# umni-ultra-controller.net
KiCad netlist of a schematic drawn in EAGLE
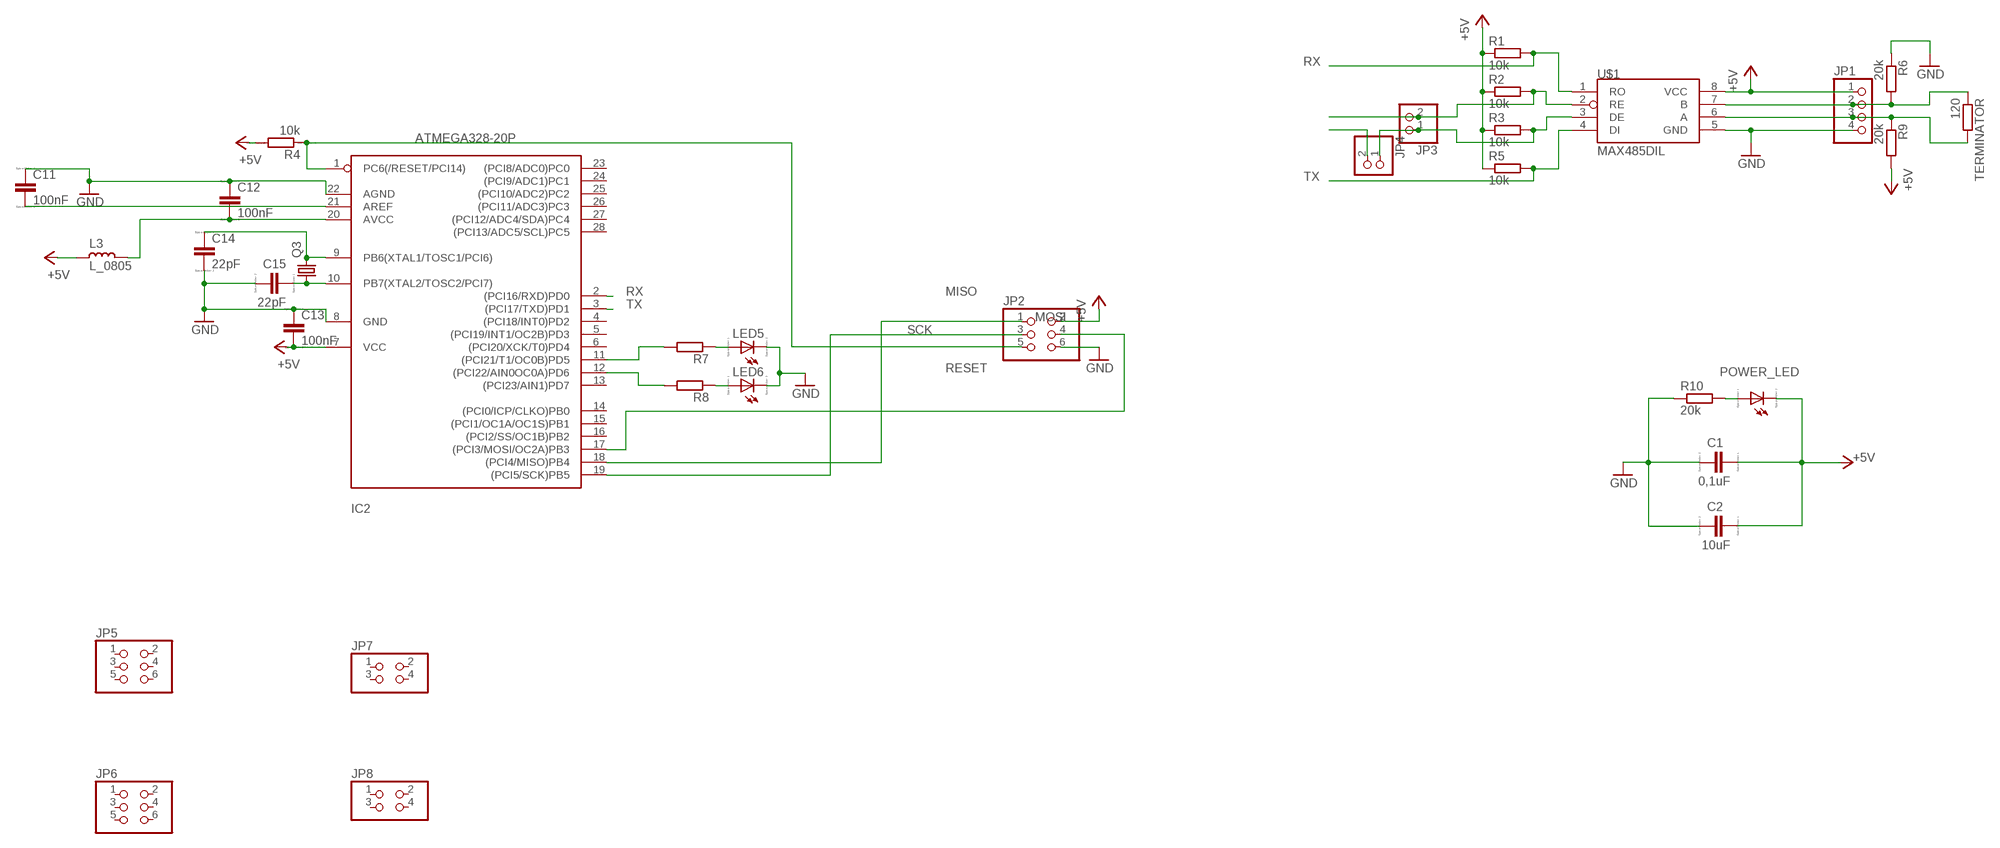
[diagram p0: schematic, sheet 1]

(export (version "E")
  (design (tool "Eeschema 10.0.6"))
  (components
    (comp (ref "C1")
      (value "0,1uF")
      (footprint "eagle-import:C1206")
      (libsource (lib "eagle-import") (part "CC1206"))
    )
    (comp (ref "C2")
      (value "10uF")
      (footprint "eagle-import:C1206")
      (libsource (lib "eagle-import") (part "CC1206"))
    )
    (comp (ref "C11")
      (value "100nF")
      (footprint "eagle-import:C1206")
      (libsource (lib "eagle-import") (part "CC1206"))
    )
    (comp (ref "C12")
      (value "100nF")
      (footprint "eagle-import:C1206")
      (libsource (lib "eagle-import") (part "CC1206"))
    )
    (comp (ref "C13")
      (value "100nF")
      (footprint "eagle-import:C1206")
      (libsource (lib "eagle-import") (part "CC1206"))
    )
    (comp (ref "C14")
      (value "22pF")
      (footprint "eagle-import:C1206")
      (libsource (lib "eagle-import") (part "CC1206"))
    )
    (comp (ref "C15")
      (value "22pF")
      (footprint "eagle-import:C1206")
      (libsource (lib "eagle-import") (part "CC1206"))
    )
    (comp (ref "IC2")
      (value "ATMEGA328-20P")
      (footprint "eagle-import:DIL28-3")
      (libsource (lib "eagle-import") (part "ATMEGA328P-20"))
    )
    (comp (ref "JP1")
      (value "PINHD-1X4")
      (footprint "eagle-import:1X04")
      (libsource (lib "eagle-import") (part "PINHD-1X4"))
    )
    (comp (ref "JP2")
      (value "PINHD-2X3")
      (footprint "eagle-import:2X03")
      (libsource (lib "eagle-import") (part "PINHD-2X3"))
    )
    (comp (ref "JP3")
      (value "PINHD-1X2")
      (footprint "eagle-import:1X02")
      (libsource (lib "eagle-import") (part "PINHD-1X2"))
    )
    (comp (ref "JP4")
      (value "PINHD-1X2")
      (footprint "eagle-import:1X02")
      (libsource (lib "eagle-import") (part "PINHD-1X2"))
    )
    (comp (ref "JP5")
      (value "PINHD-2X3")
      (footprint "eagle-import:2X03")
      (libsource (lib "eagle-import") (part "PINHD-2X3"))
    )
    (comp (ref "JP6")
      (value "PINHD-2X3")
      (footprint "eagle-import:2X03")
      (libsource (lib "eagle-import") (part "PINHD-2X3"))
    )
    (comp (ref "JP7")
      (value "PINHD-2X2")
      (footprint "eagle-import:2X02")
      (libsource (lib "eagle-import") (part "PINHD-2X2"))
    )
    (comp (ref "JP8")
      (value "PINHD-2X2")
      (footprint "eagle-import:2X02")
      (libsource (lib "eagle-import") (part "PINHD-2X2"))
    )
    (comp (ref "L3")
      (value "L_0805")
      (footprint "eagle-import:L0805")
      (libsource (lib "eagle-import") (part "L_0805"))
    )
    (comp (ref "LED5")
      (value "LED_E")
      (footprint "eagle-import:LED_1206")
      (libsource (lib "eagle-import") (part "LED_E"))
    )
    (comp (ref "LED6")
      (value "LED_E")
      (footprint "eagle-import:LED_1206")
      (libsource (lib "eagle-import") (part "LED_E"))
    )
    (comp (ref "POWER_LED")
      (value "LED_E")
      (footprint "eagle-import:LED_1206")
      (libsource (lib "eagle-import") (part "LED_E"))
    )
    (comp (ref "Q3")
      (value "CRYSTALHC49U-V")
      (footprint "eagle-import:HC49U-V")
      (libsource (lib "eagle-import") (part "CRYSTALHC49U-V"))
    )
    (comp (ref "R1")
      (value "10k")
      (footprint "eagle-import:R1206")
      (libsource (lib "eagle-import") (part "R-EU_R1206"))
    )
    (comp (ref "R2")
      (value "10k")
      (footprint "eagle-import:R1206")
      (libsource (lib "eagle-import") (part "R-EU_R1206"))
    )
    (comp (ref "R3")
      (value "10k")
      (footprint "eagle-import:R1206")
      (libsource (lib "eagle-import") (part "R-EU_R1206"))
    )
    (comp (ref "R4")
      (value "10k")
      (footprint "eagle-import:R1206")
      (libsource (lib "eagle-import") (part "RR1206"))
    )
    (comp (ref "R5")
      (value "10k")
      (footprint "eagle-import:R1206")
      (libsource (lib "eagle-import") (part "R-EU_R1206"))
    )
    (comp (ref "R6")
      (value "20k")
      (footprint "eagle-import:R1206")
      (libsource (lib "eagle-import") (part "R-EU_R1206"))
    )
    (comp (ref "R7")
      (value "R-EU_R1206")
      (footprint "eagle-import:R1206")
      (libsource (lib "eagle-import") (part "R-EU_R1206"))
    )
    (comp (ref "R8")
      (value "R-EU_R1206")
      (footprint "eagle-import:R1206")
      (libsource (lib "eagle-import") (part "R-EU_R1206"))
    )
    (comp (ref "R9")
      (value "20k")
      (footprint "eagle-import:R1206")
      (libsource (lib "eagle-import") (part "R-EU_R1206"))
    )
    (comp (ref "R10")
      (value "20k")
      (footprint "eagle-import:R1206")
      (libsource (lib "eagle-import") (part "R-EU_R1206"))
    )
    (comp (ref "TERMINATOR")
      (value "120")
      (footprint "eagle-import:R1206")
      (libsource (lib "eagle-import") (part "R-EU_R1206"))
    )
    (comp (ref "U$1")
      (value "MAX485DIL")
      (footprint "eagle-import:DIL08")
      (fields (field (name "MF") "Maxim Integrated") (field (name "MP") "MAX485"))
      (libsource (lib "eagle-import") (part "MAX485DIL"))
    )
  )
  (nets
    (net (code "1") (name "+5V") (class "Default")
      (node (ref "C1") (pin "1") (pinfunction "1_1") (pintype "passive"))
      (node (ref "C13") (pin "2") (pinfunction "2_2") (pintype "passive"))
      (node (ref "C2") (pin "1") (pinfunction "1_1") (pintype "passive"))
      (node (ref "IC2") (pin "7") (pinfunction "VCC_7") (pintype "bidirectional"))
      (node (ref "JP1") (pin "1") (pinfunction "1_1") (pintype "passive"))
      (node (ref "JP2") (pin "2") (pinfunction "2_2") (pintype "passive"))
      (node (ref "L3") (pin "2") (pinfunction "2_2") (pintype "passive"))
      (node (ref "POWER_LED") (pin "C") (pinfunction "C_C") (pintype "passive"))
      (node (ref "R1") (pin "1") (pinfunction "1_1") (pintype "passive"))
      (node (ref "R2") (pin "1") (pinfunction "1_1") (pintype "passive"))
      (node (ref "R3") (pin "1") (pinfunction "1_1") (pintype "passive"))
      (node (ref "R4") (pin "2") (pinfunction "2_2") (pintype "passive"))
      (node (ref "R5") (pin "1") (pinfunction "1_1") (pintype "passive"))
      (node (ref "R9") (pin "2") (pinfunction "2_2") (pintype "passive"))
      (node (ref "U$1") (pin "8") (pinfunction "VCC_8") (pintype "bidirectional"))
    )
    (net (code "2") (name "/MISO") (class "Default")
      (node (ref "IC2") (pin "18") (pinfunction "(PCI4/MISO)PB4_18") (pintype "bidirectional"))
      (node (ref "JP2") (pin "1") (pinfunction "1_1") (pintype "passive"))
    )
    (net (code "3") (name "/MOSI") (class "Default")
      (node (ref "IC2") (pin "17") (pinfunction "(PCI3/MOSI/OC2A)PB3_17") (pintype "bidirectional"))
      (node (ref "JP2") (pin "4") (pinfunction "4_4") (pintype "passive"))
    )
    (net (code "4") (name "/RESET") (class "Default")
      (node (ref "IC2") (pin "1") (pinfunction "PC6(/RESET/PCI14)_1") (pintype "bidirectional"))
      (node (ref "JP2") (pin "5") (pinfunction "5_5") (pintype "passive"))
      (node (ref "R4") (pin "1") (pinfunction "1_1") (pintype "passive"))
    )
    (net (code "5") (name "/RX") (class "Default")
      (node (ref "IC2") (pin "2") (pinfunction "(PCI16/RXD)PD0_2") (pintype "bidirectional"))
      (node (ref "R1") (pin "2") (pinfunction "2_2") (pintype "passive"))
      (node (ref "U$1") (pin "1") (pinfunction "RO_1") (pintype "bidirectional"))
    )
    (net (code "6") (name "/SCK") (class "Default")
      (node (ref "IC2") (pin "19") (pinfunction "(PCI5/SCK)PB5_19") (pintype "bidirectional"))
      (node (ref "JP2") (pin "3") (pinfunction "3_3") (pintype "passive"))
    )
    (net (code "7") (name "/TX") (class "Default")
      (node (ref "IC2") (pin "3") (pinfunction "(PCI17/TXD)PD1_3") (pintype "bidirectional"))
      (node (ref "R5") (pin "2") (pinfunction "2_2") (pintype "passive"))
      (node (ref "U$1") (pin "4") (pinfunction "DI_4") (pintype "bidirectional"))
    )
    (net (code "8") (name "GND") (class "Default")
      (node (ref "C1") (pin "2") (pinfunction "2_2") (pintype "passive"))
      (node (ref "C11") (pin "1") (pinfunction "1_1") (pintype "passive"))
      (node (ref "C12") (pin "1") (pinfunction "1_1") (pintype "passive"))
      (node (ref "C13") (pin "1") (pinfunction "1_1") (pintype "passive"))
      (node (ref "C14") (pin "2") (pinfunction "2_2") (pintype "passive"))
      (node (ref "C15") (pin "2") (pinfunction "2_2") (pintype "passive"))
      (node (ref "C2") (pin "2") (pinfunction "2_2") (pintype "passive"))
      (node (ref "IC2") (pin "22") (pinfunction "AGND_22") (pintype "bidirectional"))
      (node (ref "IC2") (pin "8") (pinfunction "GND_8") (pintype "bidirectional"))
      (node (ref "JP1") (pin "4") (pinfunction "4_4") (pintype "passive"))
      (node (ref "JP2") (pin "6") (pinfunction "6_6") (pintype "passive"))
      (node (ref "LED5") (pin "C") (pinfunction "C_C") (pintype "passive"))
      (node (ref "LED6") (pin "C") (pinfunction "C_C") (pintype "passive"))
      (node (ref "R10") (pin "1") (pinfunction "1_1") (pintype "passive"))
      (node (ref "R6") (pin "1") (pinfunction "1_1") (pintype "passive"))
      (node (ref "U$1") (pin "5") (pinfunction "GND_5") (pintype "bidirectional"))
    )
    (net (code "9") (name "Net-(IC2-(PCI21{slash}T1{slash}OC0B)PD5)") (class "Default")
      (node (ref "IC2") (pin "11") (pinfunction "(PCI21/T1/OC0B)PD5_11") (pintype "bidirectional"))
      (node (ref "R7") (pin "2") (pinfunction "2_2") (pintype "passive"))
    )
    (net (code "10") (name "Net-(IC2-(PCI22{slash}AIN0OC0A)PD6)") (class "Default")
      (node (ref "IC2") (pin "12") (pinfunction "(PCI22/AIN0OC0A)PD6_12") (pintype "bidirectional"))
      (node (ref "R8") (pin "2") (pinfunction "2_2") (pintype "passive"))
    )
    (net (code "11") (name "Net-(IC2-AREF)") (class "Default")
      (node (ref "C11") (pin "2") (pinfunction "2_2") (pintype "passive"))
      (node (ref "IC2") (pin "21") (pinfunction "AREF_21") (pintype "bidirectional"))
    )
    (net (code "12") (name "Net-(IC2-AVCC)") (class "Default")
      (node (ref "C12") (pin "2") (pinfunction "2_2") (pintype "passive"))
      (node (ref "IC2") (pin "20") (pinfunction "AVCC_20") (pintype "bidirectional"))
      (node (ref "L3") (pin "1") (pinfunction "1_1") (pintype "passive"))
    )
    (net (code "13") (name "Net-(IC2-PB6(XTAL1{slash}TOSC1{slash}PCI6))") (class "Default")
      (node (ref "C14") (pin "1") (pinfunction "1_1") (pintype "passive"))
      (node (ref "IC2") (pin "9") (pinfunction "PB6(XTAL1/TOSC1/PCI6)_9") (pintype "bidirectional"))
      (node (ref "Q3") (pin "2") (pinfunction "2_2") (pintype "passive"))
    )
    (net (code "14") (name "Net-(IC2-PB7(XTAL2{slash}TOSC2{slash}PCI7))") (class "Default")
      (node (ref "C15") (pin "1") (pinfunction "1_1") (pintype "passive"))
      (node (ref "IC2") (pin "10") (pinfunction "PB7(XTAL2/TOSC2/PCI7)_10") (pintype "bidirectional"))
      (node (ref "Q3") (pin "1") (pinfunction "1_1") (pintype "passive"))
    )
    (net (code "15") (name "Net-(LED5-PadA)") (class "Default")
      (node (ref "LED5") (pin "A") (pinfunction "A_A") (pintype "passive"))
      (node (ref "R7") (pin "1") (pinfunction "1_1") (pintype "passive"))
    )
    (net (code "16") (name "Net-(LED6-PadA)") (class "Default")
      (node (ref "LED6") (pin "A") (pinfunction "A_A") (pintype "passive"))
      (node (ref "R8") (pin "1") (pinfunction "1_1") (pintype "passive"))
    )
    (net (code "17") (name "Net-(POWER_LED-PadA)") (class "Default")
      (node (ref "POWER_LED") (pin "A") (pinfunction "A_A") (pintype "passive"))
      (node (ref "R10") (pin "2") (pinfunction "2_2") (pintype "passive"))
    )
    (net (code "18") (name "Net-(U$1-A)") (class "Default")
      (node (ref "JP1") (pin "3") (pinfunction "3_3") (pintype "passive"))
      (node (ref "R9") (pin "1") (pinfunction "1_1") (pintype "passive"))
      (node (ref "TERMINATOR") (pin "2") (pinfunction "2_2") (pintype "passive"))
      (node (ref "U$1") (pin "6") (pinfunction "A_6") (pintype "bidirectional"))
    )
    (net (code "19") (name "Net-(U$1-B)") (class "Default")
      (node (ref "JP1") (pin "2") (pinfunction "2_2") (pintype "passive"))
      (node (ref "R6") (pin "2") (pinfunction "2_2") (pintype "passive"))
      (node (ref "TERMINATOR") (pin "1") (pinfunction "1_1") (pintype "passive"))
      (node (ref "U$1") (pin "7") (pinfunction "B_7") (pintype "bidirectional"))
    )
    (net (code "20") (name "Net-(U$1-DE)") (class "Default")
      (node (ref "JP3") (pin "1") (pinfunction "1_1") (pintype "passive"))
      (node (ref "JP4") (pin "1") (pinfunction "1_1") (pintype "passive"))
      (node (ref "R3") (pin "2") (pinfunction "2_2") (pintype "passive"))
      (node (ref "U$1") (pin "3") (pinfunction "DE_3") (pintype "bidirectional"))
    )
    (net (code "21") (name "Net-(U$1-RE)") (class "Default")
      (node (ref "JP3") (pin "2") (pinfunction "2_2") (pintype "passive"))
      (node (ref "R2") (pin "2") (pinfunction "2_2") (pintype "passive"))
      (node (ref "U$1") (pin "2") (pinfunction "RE_2") (pintype "bidirectional"))
    )
    (net (code "22") (name "unconnected-(IC2-(PCI0{slash}ICP{slash}CLKO)PB0-Pad14)") (class "Default")
      (node (ref "IC2") (pin "14") (pinfunction "(PCI0/ICP/CLKO)PB0_14") (pintype "bidirectional"))
    )
    (net (code "23") (name "unconnected-(IC2-(PCI1{slash}OC1A{slash}OC1S)PB1-Pad15)") (class "Default")
      (node (ref "IC2") (pin "15") (pinfunction "(PCI1/OC1A/OC1S)PB1_15") (pintype "bidirectional"))
    )
    (net (code "24") (name "unconnected-(IC2-(PCI2{slash}SS{slash}OC1B)PB2-Pad16)") (class "Default")
      (node (ref "IC2") (pin "16") (pinfunction "(PCI2/SS/OC1B)PB2_16") (pintype "bidirectional"))
    )
    (net (code "25") (name "unconnected-(IC2-(PCI8{slash}ADC0)PC0-Pad23)") (class "Default")
      (node (ref "IC2") (pin "23") (pinfunction "(PCI8/ADC0)PC0_23") (pintype "bidirectional"))
    )
    (net (code "26") (name "unconnected-(IC2-(PCI9{slash}ADC1)PC1-Pad24)") (class "Default")
      (node (ref "IC2") (pin "24") (pinfunction "(PCI9/ADC1)PC1_24") (pintype "bidirectional"))
    )
    (net (code "27") (name "unconnected-(IC2-(PCI10{slash}ADC2)PC2-Pad25)") (class "Default")
      (node (ref "IC2") (pin "25") (pinfunction "(PCI10/ADC2)PC2_25") (pintype "bidirectional"))
    )
    (net (code "28") (name "unconnected-(IC2-(PCI11{slash}ADC3)PC3-Pad26)") (class "Default")
      (node (ref "IC2") (pin "26") (pinfunction "(PCI11/ADC3)PC3_26") (pintype "bidirectional"))
    )
    (net (code "29") (name "unconnected-(IC2-(PCI12{slash}ADC4{slash}SDA)PC4-Pad27)") (class "Default")
      (node (ref "IC2") (pin "27") (pinfunction "(PCI12/ADC4/SDA)PC4_27") (pintype "bidirectional"))
    )
    (net (code "30") (name "unconnected-(IC2-(PCI13{slash}ADC5{slash}SCL)PC5-Pad28)") (class "Default")
      (node (ref "IC2") (pin "28") (pinfunction "(PCI13/ADC5/SCL)PC5_28") (pintype "bidirectional"))
    )
    (net (code "31") (name "unconnected-(IC2-(PCI18{slash}INT0)PD2-Pad4)") (class "Default")
      (node (ref "IC2") (pin "4") (pinfunction "(PCI18/INT0)PD2_4") (pintype "bidirectional"))
    )
    (net (code "32") (name "unconnected-(IC2-(PCI19{slash}INT1{slash}OC2B)PD3-Pad5)") (class "Default")
      (node (ref "IC2") (pin "5") (pinfunction "(PCI19/INT1/OC2B)PD3_5") (pintype "bidirectional"))
    )
    (net (code "33") (name "unconnected-(IC2-(PCI20{slash}XCK{slash}T0)PD4-Pad6)") (class "Default")
      (node (ref "IC2") (pin "6") (pinfunction "(PCI20/XCK/T0)PD4_6") (pintype "bidirectional"))
    )
    (net (code "34") (name "unconnected-(IC2-(PCI23{slash}AIN1)PD7-Pad13)") (class "Default")
      (node (ref "IC2") (pin "13") (pinfunction "(PCI23/AIN1)PD7_13") (pintype "bidirectional"))
    )
    (net (code "35") (name "unconnected-(JP4-Pad2)") (class "Default")
      (node (ref "JP4") (pin "2") (pinfunction "2_2") (pintype "passive"))
    )
    (net (code "36") (name "unconnected-(JP5-Pad1)") (class "Default")
      (node (ref "JP5") (pin "1") (pinfunction "1_1") (pintype "passive"))
    )
    (net (code "37") (name "unconnected-(JP5-Pad2)") (class "Default")
      (node (ref "JP5") (pin "2") (pinfunction "2_2") (pintype "passive"))
    )
    (net (code "38") (name "unconnected-(JP5-Pad3)") (class "Default")
      (node (ref "JP5") (pin "3") (pinfunction "3_3") (pintype "passive"))
    )
    (net (code "39") (name "unconnected-(JP5-Pad4)") (class "Default")
      (node (ref "JP5") (pin "4") (pinfunction "4_4") (pintype "passive"))
    )
    (net (code "40") (name "unconnected-(JP5-Pad5)") (class "Default")
      (node (ref "JP5") (pin "5") (pinfunction "5_5") (pintype "passive"))
    )
    (net (code "41") (name "unconnected-(JP5-Pad6)") (class "Default")
      (node (ref "JP5") (pin "6") (pinfunction "6_6") (pintype "passive"))
    )
    (net (code "42") (name "unconnected-(JP6-Pad1)") (class "Default")
      (node (ref "JP6") (pin "1") (pinfunction "1_1") (pintype "passive"))
    )
    (net (code "43") (name "unconnected-(JP6-Pad2)") (class "Default")
      (node (ref "JP6") (pin "2") (pinfunction "2_2") (pintype "passive"))
    )
    (net (code "44") (name "unconnected-(JP6-Pad3)") (class "Default")
      (node (ref "JP6") (pin "3") (pinfunction "3_3") (pintype "passive"))
    )
    (net (code "45") (name "unconnected-(JP6-Pad4)") (class "Default")
      (node (ref "JP6") (pin "4") (pinfunction "4_4") (pintype "passive"))
    )
    (net (code "46") (name "unconnected-(JP6-Pad5)") (class "Default")
      (node (ref "JP6") (pin "5") (pinfunction "5_5") (pintype "passive"))
    )
    (net (code "47") (name "unconnected-(JP6-Pad6)") (class "Default")
      (node (ref "JP6") (pin "6") (pinfunction "6_6") (pintype "passive"))
    )
    (net (code "48") (name "unconnected-(JP7-Pad1)") (class "Default")
      (node (ref "JP7") (pin "1") (pinfunction "1_1") (pintype "passive"))
    )
    (net (code "49") (name "unconnected-(JP7-Pad2)") (class "Default")
      (node (ref "JP7") (pin "2") (pinfunction "2_2") (pintype "passive"))
    )
    (net (code "50") (name "unconnected-(JP7-Pad3)") (class "Default")
      (node (ref "JP7") (pin "3") (pinfunction "3_3") (pintype "passive"))
    )
    (net (code "51") (name "unconnected-(JP7-Pad4)") (class "Default")
      (node (ref "JP7") (pin "4") (pinfunction "4_4") (pintype "passive"))
    )
    (net (code "52") (name "unconnected-(JP8-Pad1)") (class "Default")
      (node (ref "JP8") (pin "1") (pinfunction "1_1") (pintype "passive"))
    )
    (net (code "53") (name "unconnected-(JP8-Pad2)") (class "Default")
      (node (ref "JP8") (pin "2") (pinfunction "2_2") (pintype "passive"))
    )
    (net (code "54") (name "unconnected-(JP8-Pad3)") (class "Default")
      (node (ref "JP8") (pin "3") (pinfunction "3_3") (pintype "passive"))
    )
    (net (code "55") (name "unconnected-(JP8-Pad4)") (class "Default")
      (node (ref "JP8") (pin "4") (pinfunction "4_4") (pintype "passive"))
    )
  )
)
